# board.net
KiCad netlist of a schematic drawn in EAGLE
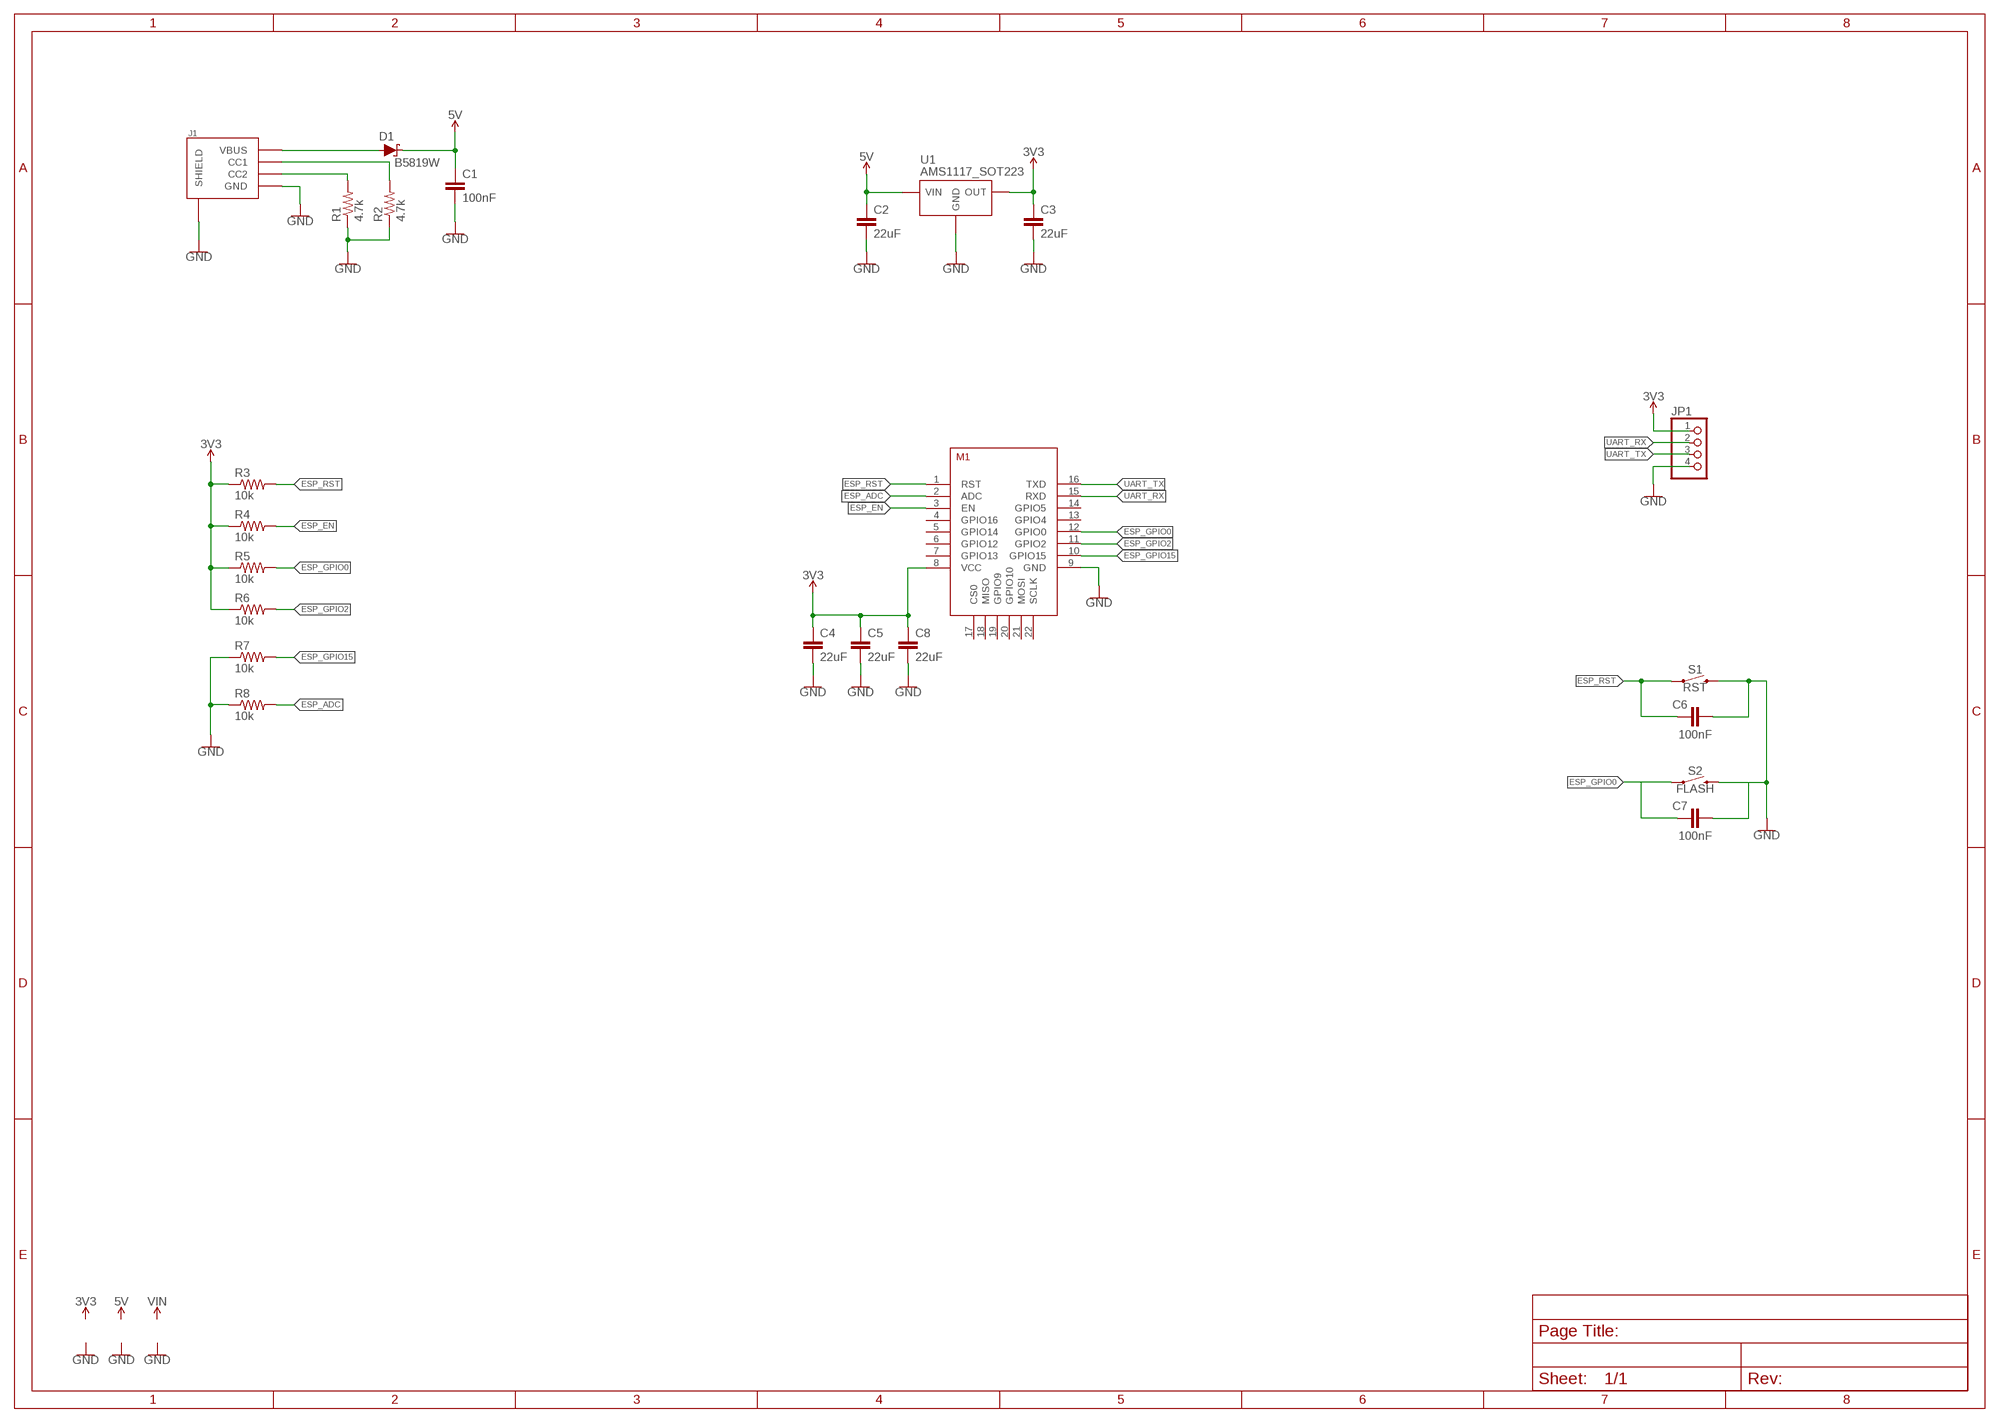
[diagram p0: schematic, sheet 1]

(export (version "E")
  (design (tool "Eeschema 10.0.6"))
  (components
    (comp (ref "C1")
      (value "100nF")
      (footprint "eagle-import:C0402")
      (libsource (lib "eagle-import") (part "C-NON-POLC0402"))
    )
    (comp (ref "C2")
      (value "22uF")
      (footprint "eagle-import:C0805")
      (libsource (lib "eagle-import") (part "C-NON-POLC0805"))
    )
    (comp (ref "C3")
      (value "22uF")
      (footprint "eagle-import:C0805")
      (libsource (lib "eagle-import") (part "C-NON-POLC0805"))
    )
    (comp (ref "C4")
      (value "22uF")
      (footprint "eagle-import:C0805")
      (libsource (lib "eagle-import") (part "C-NON-POLC0805"))
    )
    (comp (ref "C5")
      (value "22uF")
      (footprint "eagle-import:C0805")
      (libsource (lib "eagle-import") (part "C-NON-POLC0805"))
    )
    (comp (ref "C6")
      (value "100nF")
      (footprint "eagle-import:C0402")
      (libsource (lib "eagle-import") (part "C-NON-POLC0402"))
    )
    (comp (ref "C7")
      (value "100nF")
      (footprint "eagle-import:C0402")
      (libsource (lib "eagle-import") (part "C-NON-POLC0402"))
    )
    (comp (ref "C8")
      (value "22uF")
      (footprint "eagle-import:C0805")
      (libsource (lib "eagle-import") (part "C-NON-POLC0805"))
    )
    (comp (ref "D1")
      (value "B5819W")
      (footprint "eagle-import:SOD-123")
      (libsource (lib "eagle-import") (part "DIODE-SCHOTTKY_SOD-123"))
    )
    (comp (ref "J1")
      (value "USB-TYPE-C-31-M-17")
      (footprint "eagle-import:USB-TYPE-C-31-M-17")
      (libsource (lib "eagle-import") (part "USB-TYPE-C-31-M-17"))
    )
    (comp (ref "JP1")
      (value "PINHD-1X4")
      (footprint "eagle-import:1X04")
      (libsource (lib "eagle-import") (part "PINHD-1X4"))
    )
    (comp (ref "M1")
      (value "ESP8266-12E")
      (footprint "eagle-import:ESP8266-ESP12E")
      (libsource (lib "eagle-import") (part "ESP8266-12E"))
    )
    (comp (ref "R1")
      (value "4.7k")
      (footprint "eagle-import:R0402")
      (libsource (lib "eagle-import") (part "RR0402"))
    )
    (comp (ref "R2")
      (value "4.7k")
      (footprint "eagle-import:R0402")
      (libsource (lib "eagle-import") (part "RR0402"))
    )
    (comp (ref "R3")
      (value "10k")
      (footprint "eagle-import:R0402")
      (libsource (lib "eagle-import") (part "RR0402"))
    )
    (comp (ref "R4")
      (value "10k")
      (footprint "eagle-import:R0402")
      (libsource (lib "eagle-import") (part "RR0402"))
    )
    (comp (ref "R5")
      (value "10k")
      (footprint "eagle-import:R0402")
      (libsource (lib "eagle-import") (part "RR0402"))
    )
    (comp (ref "R6")
      (value "10k")
      (footprint "eagle-import:R0402")
      (libsource (lib "eagle-import") (part "RR0402"))
    )
    (comp (ref "R7")
      (value "10k")
      (footprint "eagle-import:R0402")
      (libsource (lib "eagle-import") (part "RR0402"))
    )
    (comp (ref "R8")
      (value "10k")
      (footprint "eagle-import:R0402")
      (libsource (lib "eagle-import") (part "RR0402"))
    )
    (comp (ref "S1")
      (value "RST")
      (footprint "eagle-import:TACTILE_SWITCH_SMD_3.0X4.0MM")
      (libsource (lib "eagle-import") (part "SWITCH-SPST-SMD-3.0X4.0MM"))
    )
    (comp (ref "S2")
      (value "FLASH")
      (footprint "eagle-import:TACTILE_SWITCH_SMD_3.0X4.0MM")
      (libsource (lib "eagle-import") (part "SWITCH-SPST-SMD-3.0X4.0MM"))
    )
    (comp (ref "U1")
      (value "AMS1117_SOT223")
      (footprint "eagle-import:SOT-223")
      (libsource (lib "eagle-import") (part "AMS1117_SOT223"))
    )
  )
  (nets
    (net (code "1") (name "3V3") (class "Default")
      (node (ref "C3") (pin "1") (pinfunction "1_1") (pintype "passive"))
      (node (ref "C4") (pin "1") (pinfunction "1_1") (pintype "passive"))
      (node (ref "C5") (pin "1") (pinfunction "1_1") (pintype "passive"))
      (node (ref "C8") (pin "1") (pinfunction "1_1") (pintype "passive"))
      (node (ref "JP1") (pin "1") (pinfunction "1_1") (pintype "passive"))
      (node (ref "M1") (pin "8") (pinfunction "VCC_8") (pintype "bidirectional"))
      (node (ref "R3") (pin "1") (pinfunction "1_1") (pintype "passive"))
      (node (ref "R4") (pin "1") (pinfunction "1_1") (pintype "passive"))
      (node (ref "R5") (pin "1") (pinfunction "1_1") (pintype "passive"))
      (node (ref "R6") (pin "1") (pinfunction "1_1") (pintype "passive"))
      (node (ref "U1") (pin "2") (pinfunction "OUT_2") (pintype "bidirectional"))
      (node (ref "U1") (pin "4") (pinfunction "OUT_4") (pintype "bidirectional"))
    )
    (net (code "2") (name "5V") (class "Default")
      (node (ref "C1") (pin "1") (pinfunction "1_1") (pintype "passive"))
      (node (ref "C2") (pin "1") (pinfunction "1_1") (pintype "passive"))
      (node (ref "D1") (pin "C") (pinfunction "C_C") (pintype "passive"))
      (node (ref "U1") (pin "3") (pinfunction "VIN_3") (pintype "bidirectional"))
    )
    (net (code "3") (name "ESP_ADC") (class "Default")
      (node (ref "M1") (pin "2") (pinfunction "ADC_2") (pintype "bidirectional"))
      (node (ref "R8") (pin "2") (pinfunction "2_2") (pintype "passive"))
    )
    (net (code "4") (name "ESP_EN") (class "Default")
      (node (ref "M1") (pin "3") (pinfunction "EN_3") (pintype "bidirectional"))
      (node (ref "R4") (pin "2") (pinfunction "2_2") (pintype "passive"))
    )
    (net (code "5") (name "ESP_GPIO0") (class "Default")
      (node (ref "M1") (pin "12") (pinfunction "GPIO0_12") (pintype "bidirectional"))
      (node (ref "R5") (pin "2") (pinfunction "2_2") (pintype "passive"))
      (node (ref "S2") (pin "1") (pinfunction "1_1") (pintype "passive"))
    )
    (net (code "6") (name "ESP_GPIO2") (class "Default")
      (node (ref "M1") (pin "11") (pinfunction "GPIO2_11") (pintype "bidirectional"))
      (node (ref "R6") (pin "2") (pinfunction "2_2") (pintype "passive"))
    )
    (net (code "7") (name "ESP_GPIO15") (class "Default")
      (node (ref "M1") (pin "10") (pinfunction "GPIO15_10") (pintype "bidirectional"))
      (node (ref "R7") (pin "2") (pinfunction "2_2") (pintype "passive"))
    )
    (net (code "8") (name "ESP_RST") (class "Default")
      (node (ref "C6") (pin "1") (pinfunction "1_1") (pintype "passive"))
      (node (ref "M1") (pin "1") (pinfunction "RST_1") (pintype "bidirectional"))
      (node (ref "R3") (pin "2") (pinfunction "2_2") (pintype "passive"))
      (node (ref "S1") (pin "1") (pinfunction "1_1") (pintype "passive"))
    )
    (net (code "9") (name "GND") (class "Default")
      (node (ref "C1") (pin "2") (pinfunction "2_2") (pintype "passive"))
      (node (ref "C2") (pin "2") (pinfunction "2_2") (pintype "passive"))
      (node (ref "C3") (pin "2") (pinfunction "2_2") (pintype "passive"))
      (node (ref "C4") (pin "2") (pinfunction "2_2") (pintype "passive"))
      (node (ref "C5") (pin "2") (pinfunction "2_2") (pintype "passive"))
      (node (ref "C6") (pin "2") (pinfunction "2_2") (pintype "passive"))
      (node (ref "C8") (pin "2") (pinfunction "2_2") (pintype "passive"))
      (node (ref "J1") (pin "GND") (pinfunction "GND_GND") (pintype "bidirectional"))
      (node (ref "J1") (pin "GND_2") (pinfunction "GND_GND_2") (pintype "bidirectional"))
      (node (ref "J1") (pin "SHLD-B1") (pinfunction "SHIELD_SHLD-B1") (pintype "bidirectional"))
      (node (ref "J1") (pin "SHLD-B2") (pinfunction "SHIELD_SHLD-B2") (pintype "bidirectional"))
      (node (ref "J1") (pin "SHLD-B3") (pinfunction "SHIELD_SHLD-B3") (pintype "bidirectional"))
      (node (ref "J1") (pin "SHLD-B4") (pinfunction "SHIELD_SHLD-B4") (pintype "bidirectional"))
      (node (ref "J1") (pin "SHLD-T1") (pinfunction "SHIELD_SHLD-T1") (pintype "bidirectional"))
      (node (ref "J1") (pin "SHLD-T2") (pinfunction "SHIELD_SHLD-T2") (pintype "bidirectional"))
      (node (ref "J1") (pin "SHLD-T3") (pinfunction "SHIELD_SHLD-T3") (pintype "bidirectional"))
      (node (ref "J1") (pin "SHLD-T4") (pinfunction "SHIELD_SHLD-T4") (pintype "bidirectional"))
      (node (ref "JP1") (pin "4") (pinfunction "4_4") (pintype "passive"))
      (node (ref "M1") (pin "9") (pinfunction "GND_9") (pintype "bidirectional"))
      (node (ref "R1") (pin "1") (pinfunction "1_1") (pintype "passive"))
      (node (ref "R2") (pin "1") (pinfunction "1_1") (pintype "passive"))
      (node (ref "R7") (pin "1") (pinfunction "1_1") (pintype "passive"))
      (node (ref "R8") (pin "1") (pinfunction "1_1") (pintype "passive"))
      (node (ref "S1") (pin "2") (pinfunction "2_2") (pintype "passive"))
      (node (ref "S2") (pin "2") (pinfunction "2_2") (pintype "passive"))
      (node (ref "U1") (pin "1") (pinfunction "GND_1") (pintype "bidirectional"))
    )
    (net (code "10") (name "Net-(D1-PadA)") (class "Default")
      (node (ref "D1") (pin "A") (pinfunction "A_A") (pintype "passive"))
      (node (ref "J1") (pin "VBUS") (pinfunction "VBUS_VBUS") (pintype "bidirectional"))
      (node (ref "J1") (pin "VBUS_2") (pinfunction "VBUS_VBUS_2") (pintype "bidirectional"))
    )
    (net (code "11") (name "Net-(J1-PadCC1)") (class "Default")
      (node (ref "J1") (pin "CC1") (pinfunction "CC1_CC1") (pintype "bidirectional"))
      (node (ref "R2") (pin "2") (pinfunction "2_2") (pintype "passive"))
    )
    (net (code "12") (name "Net-(J1-PadCC2)") (class "Default")
      (node (ref "J1") (pin "CC2") (pinfunction "CC2_CC2") (pintype "bidirectional"))
      (node (ref "R1") (pin "2") (pinfunction "2_2") (pintype "passive"))
    )
    (net (code "13") (name "UART_RX") (class "Default")
      (node (ref "JP1") (pin "2") (pinfunction "2_2") (pintype "passive"))
      (node (ref "M1") (pin "15") (pinfunction "RXD_15") (pintype "bidirectional"))
    )
    (net (code "14") (name "UART_TX") (class "Default")
      (node (ref "JP1") (pin "3") (pinfunction "3_3") (pintype "passive"))
      (node (ref "M1") (pin "16") (pinfunction "TXD_16") (pintype "bidirectional"))
    )
    (net (code "16") (name "unconnected-(C7-Pad1)") (class "Default")
      (node (ref "C7") (pin "1") (pinfunction "1_1") (pintype "passive"))
    )
    (net (code "17") (name "unconnected-(C7-Pad2)") (class "Default")
      (node (ref "C7") (pin "2") (pinfunction "2_2") (pintype "passive"))
    )
    (net (code "18") (name "unconnected-(M1-CS0-Pad17)") (class "Default")
      (node (ref "M1") (pin "17") (pinfunction "CS0_17") (pintype "bidirectional"))
    )
    (net (code "19") (name "unconnected-(M1-GPIO4-Pad13)") (class "Default")
      (node (ref "M1") (pin "13") (pinfunction "GPIO4_13") (pintype "bidirectional"))
    )
    (net (code "20") (name "unconnected-(M1-GPIO5-Pad14)") (class "Default")
      (node (ref "M1") (pin "14") (pinfunction "GPIO5_14") (pintype "bidirectional"))
    )
    (net (code "21") (name "unconnected-(M1-GPIO9-Pad19)") (class "Default")
      (node (ref "M1") (pin "19") (pinfunction "GPIO9_19") (pintype "bidirectional"))
    )
    (net (code "22") (name "unconnected-(M1-GPIO10-Pad20)") (class "Default")
      (node (ref "M1") (pin "20") (pinfunction "GPIO10_20") (pintype "bidirectional"))
    )
    (net (code "23") (name "unconnected-(M1-GPIO12-Pad6)") (class "Default")
      (node (ref "M1") (pin "6") (pinfunction "GPIO12_6") (pintype "bidirectional"))
    )
    (net (code "24") (name "unconnected-(M1-GPIO13-Pad7)") (class "Default")
      (node (ref "M1") (pin "7") (pinfunction "GPIO13_7") (pintype "bidirectional"))
    )
    (net (code "25") (name "unconnected-(M1-GPIO14-Pad5)") (class "Default")
      (node (ref "M1") (pin "5") (pinfunction "GPIO14_5") (pintype "bidirectional"))
    )
    (net (code "26") (name "unconnected-(M1-GPIO16-Pad4)") (class "Default")
      (node (ref "M1") (pin "4") (pinfunction "GPIO16_4") (pintype "bidirectional"))
    )
    (net (code "27") (name "unconnected-(M1-MISO-Pad18)") (class "Default")
      (node (ref "M1") (pin "18") (pinfunction "MISO_18") (pintype "bidirectional"))
    )
    (net (code "28") (name "unconnected-(M1-MOSI-Pad21)") (class "Default")
      (node (ref "M1") (pin "21") (pinfunction "MOSI_21") (pintype "bidirectional"))
    )
    (net (code "29") (name "unconnected-(M1-SCLK-Pad22)") (class "Default")
      (node (ref "M1") (pin "22") (pinfunction "SCLK_22") (pintype "bidirectional"))
    )
  )
)
